# sensors.net
KiCad netlist of a schematic drawn in Altium Designer
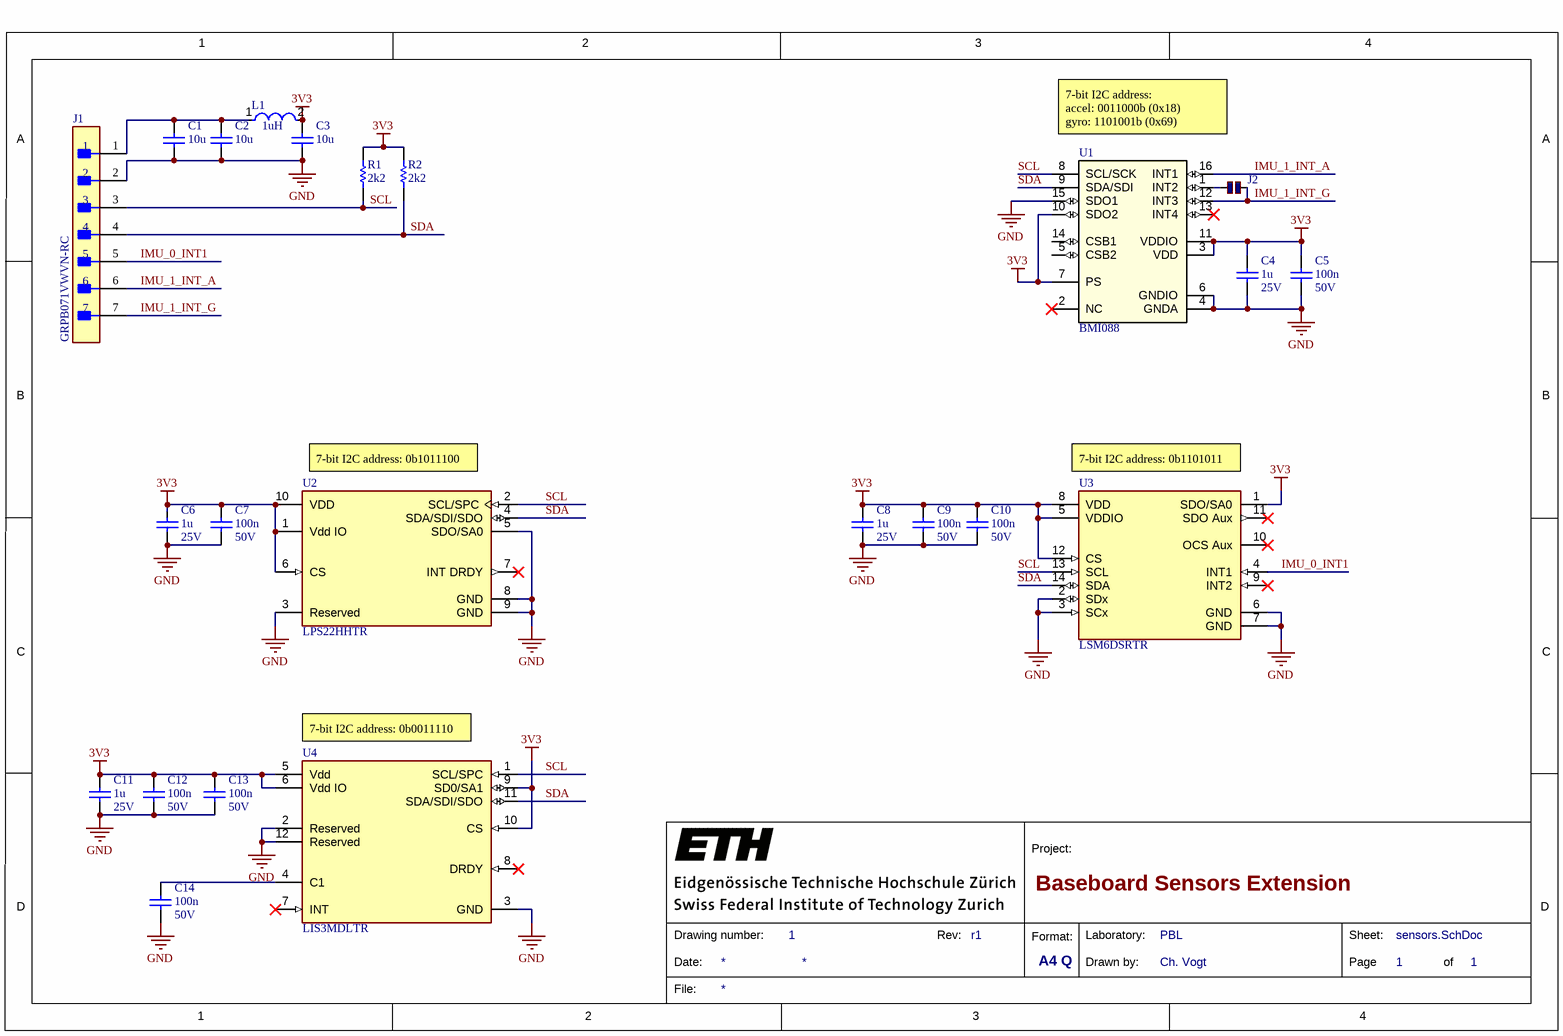
[diagram p0: sensors.SchDoc]

(export (version "E")
  (design (tool "Eeschema 10.0.6"))
  (components
    (comp (ref "C1")
      (value "10u")
      (footprint "k26_FPGA_drone_baseboard:CAPC0402")
      (fields
        (field (name "MANUFACTURER") "Samsung")
        (field (name "MANUFACTURER PART NUMBER") "CL05A106MP5NUNC")
      )
      (libsource (lib "k26_FPGA_drone_baseboard") (part "cap0402"))
    )
    (comp (ref "C2")
      (value "10u")
      (footprint "k26_FPGA_drone_baseboard:CAPC0402")
      (fields
        (field (name "MANUFACTURER") "Samsung")
        (field (name "MANUFACTURER PART NUMBER") "CL05A106MP5NUNC")
      )
      (libsource (lib "k26_FPGA_drone_baseboard") (part "cap0402"))
    )
    (comp (ref "C3")
      (value "10u")
      (footprint "k26_FPGA_drone_baseboard:CAPC0402")
      (fields
        (field (name "MANUFACTURER") "Samsung")
        (field (name "MANUFACTURER PART NUMBER") "CL05A106MP5NUNC")
      )
      (libsource (lib "k26_FPGA_drone_baseboard") (part "cap0402"))
    )
    (comp (ref "C4")
      (value "1u")
      (footprint "k26_FPGA_drone_baseboard:CAPC0402")
      (fields
        (field (name "MANUFACTURER") "Taiyo Yuden")
        (field (name "MANUFACTURER PART NUMBER") "TMK105BJ105MV-F")
        (field (name "RATED DC VOLTAGE (URDC)") "25V")
      )
      (libsource (lib "k26_FPGA_drone_baseboard") (part "cap0402"))
    )
    (comp (ref "C5")
      (value "100n")
      (footprint "k26_FPGA_drone_baseboard:CAPC0402")
      (fields
        (field (name "MANUFACTURER") "Yageo")
        (field (name "MANUFACTURER PART NUMBER") "CC0402KRX5R9BB104")
        (field (name "RATED DC VOLTAGE (URDC)") "50V")
      )
      (libsource (lib "k26_FPGA_drone_baseboard") (part "cap0402"))
    )
    (comp (ref "C6")
      (value "1u")
      (footprint "k26_FPGA_drone_baseboard:CAPC0402")
      (fields
        (field (name "MANUFACTURER") "Taiyo Yuden")
        (field (name "MANUFACTURER PART NUMBER") "TMK105BJ105MV-F")
        (field (name "RATED DC VOLTAGE (URDC)") "25V")
      )
      (libsource (lib "k26_FPGA_drone_baseboard") (part "cap0402"))
    )
    (comp (ref "C7")
      (value "100n")
      (footprint "k26_FPGA_drone_baseboard:CAPC0402")
      (fields
        (field (name "MANUFACTURER") "Yageo")
        (field (name "MANUFACTURER PART NUMBER") "CC0402KRX5R9BB104")
        (field (name "RATED DC VOLTAGE (URDC)") "50V")
      )
      (libsource (lib "k26_FPGA_drone_baseboard") (part "cap0402"))
    )
    (comp (ref "C8")
      (value "1u")
      (footprint "k26_FPGA_drone_baseboard:CAPC0402")
      (fields
        (field (name "MANUFACTURER") "Taiyo Yuden")
        (field (name "MANUFACTURER PART NUMBER") "TMK105BJ105MV-F")
        (field (name "RATED DC VOLTAGE (URDC)") "25V")
      )
      (libsource (lib "k26_FPGA_drone_baseboard") (part "cap0402"))
    )
    (comp (ref "C9")
      (value "100n")
      (footprint "k26_FPGA_drone_baseboard:CAPC0402")
      (fields
        (field (name "MANUFACTURER") "Yageo")
        (field (name "MANUFACTURER PART NUMBER") "CC0402KRX5R9BB104")
        (field (name "RATED DC VOLTAGE (URDC)") "50V")
      )
      (libsource (lib "k26_FPGA_drone_baseboard") (part "cap0402"))
    )
    (comp (ref "C10")
      (value "100n")
      (footprint "k26_FPGA_drone_baseboard:CAPC0402")
      (fields
        (field (name "MANUFACTURER") "Yageo")
        (field (name "MANUFACTURER PART NUMBER") "CC0402KRX5R9BB104")
        (field (name "RATED DC VOLTAGE (URDC)") "50V")
      )
      (libsource (lib "k26_FPGA_drone_baseboard") (part "cap0402"))
    )
    (comp (ref "C11")
      (value "1u")
      (footprint "k26_FPGA_drone_baseboard:CAPC0402")
      (fields
        (field (name "MANUFACTURER") "Taiyo Yuden")
        (field (name "MANUFACTURER PART NUMBER") "TMK105BJ105MV-F")
        (field (name "RATED DC VOLTAGE (URDC)") "25V")
      )
      (libsource (lib "k26_FPGA_drone_baseboard") (part "cap0402"))
    )
    (comp (ref "C12")
      (value "100n")
      (footprint "k26_FPGA_drone_baseboard:CAPC0402")
      (fields
        (field (name "MANUFACTURER") "Yageo")
        (field (name "MANUFACTURER PART NUMBER") "CC0402KRX5R9BB104")
        (field (name "RATED DC VOLTAGE (URDC)") "50V")
      )
      (libsource (lib "k26_FPGA_drone_baseboard") (part "cap0402"))
    )
    (comp (ref "C13")
      (value "100n")
      (footprint "k26_FPGA_drone_baseboard:CAPC0402")
      (fields
        (field (name "MANUFACTURER") "Yageo")
        (field (name "MANUFACTURER PART NUMBER") "CC0402KRX5R9BB104")
        (field (name "RATED DC VOLTAGE (URDC)") "50V")
      )
      (libsource (lib "k26_FPGA_drone_baseboard") (part "cap0402"))
    )
    (comp (ref "C14")
      (value "100n")
      (footprint "k26_FPGA_drone_baseboard:CAPC0402")
      (fields
        (field (name "MANUFACTURER") "Yageo")
        (field (name "MANUFACTURER PART NUMBER") "CC0402KRX5R9BB104")
        (field (name "RATED DC VOLTAGE (URDC)") "50V")
      )
      (libsource (lib "k26_FPGA_drone_baseboard") (part "cap0402"))
    )
    (comp (ref "J1")
      (value "GRPB071VWVN-RC")
      (footprint "FP-GRPB071VWVN-RC-MFG")
      (description "CONN HEADER VERT 7POS 1.27MM")
      (libsource (lib "Altium Content Vault") (part "5bcee6b94e1fee4be3f4cc3a650a442"))
    )
    (comp (ref "J2")
      (value "Solder Jumper")
      (footprint "Small Solder Jumper")
      (libsource (lib "ETHZ Vault") (part "Solder Jumper"))
    )
    (comp (ref "L1")
      (value "MLZ1005M1R0WT000")
      (footprint "FP-MLZ1005-MFG")
      (description "Shielded Multilayer Inductor 1uH ±20% 450mA 455mΩ SMD 0402")
      (fields (field (name "TOLERANCE") "20%") (field (name "INDUCTANCE") "1uH"))
      (libsource (lib "Altium Content Vault") (part "725321dda6339637d4d059423bc1c3c"))
    )
    (comp (ref "R1")
      (value "2k2")
      (footprint "k26_FPGA_drone_baseboard:RES0402")
      (fields
        (field (name "MANUFACTURER") "Vishay")
        (field (name "MANUFACTURER PART NUMBER") "CRCW04022K20FKED")
        (field (name "TOLERANCE") "1%")
      )
      (libsource (lib "k26_FPGA_drone_baseboard") (part "res0402"))
    )
    (comp (ref "R2")
      (value "2k2")
      (footprint "k26_FPGA_drone_baseboard:RES0402")
      (fields
        (field (name "MANUFACTURER") "Vishay")
        (field (name "MANUFACTURER PART NUMBER") "CRCW04022K20FKED")
        (field (name "TOLERANCE") "1%")
      )
      (libsource (lib "k26_FPGA_drone_baseboard") (part "res0402"))
    )
    (comp (ref "U1")
      (value "BMI088")
      (footprint "QFN_BMI085_BOS")
      (description "No Description Available")
      (fields (field (name "COPYRIGHT") "Copyright (C) 2024 Ultra Librarian. All rights reserved."))
      (libsource (lib "k26_FPGA_drone_baseboard") (part "BMI088"))
    )
    (comp (ref "U2")
      (value "LPS22HHTR")
      (footprint "FP-HLGA-10L-DM00386636-MFG")
      (description "CONSUMER MEMS")
      (fields
        (field (name "OCTOPART") "https://octopart.com/lps22hhtr-stmicroelectronics-94834025")
        (field (name "MANUFACTURER") "STMicroelectronics")
      )
      (libsource (lib "k26_FPGA_drone_baseboard") (part "af158f922cca5ffd55045a3797efeaf"))
    )
    (comp (ref "U3")
      (value "LSM6DSRTR")
      (footprint "FP-LGA-14L-DM00249496-MFG")
      (description "INEMO INERTIAL MODULE: 3D ACCELE")
      (fields
        (field (name "MANUFACTURER") "STMicroelectronics")
        (field (name "OCTOPART") "https://octopart.com/lsm6dsrtr-stmicroelectronics-93180177")
      )
      (libsource (lib "k26_FPGA_drone_baseboard") (part "CMP-12177-000003-1"))
    )
    (comp (ref "U4")
      (value "LIS3MDLTR")
      (footprint "FP-VFLGA-12-8365767-MFG")
      (description "SENSOR MR I2C/SPI 12LGA")
      (fields
        (field (name "OCTOPART") "https://octopart.com/lis3mdltr-stmicroelectronics-29403125")
        (field (name "MANUFACTURER") "STMicroelectronics")
      )
      (libsource (lib "k26_FPGA_drone_baseboard") (part "CMP-2000-07463-2"))
    )
  )
  (nets
    (net (code "1") (name "/IMU_0_INT1") (class "Default")
      (node (ref "J1") (pin "5") (pinfunction "5_5") (pintype "passive"))
      (node (ref "U3") (pin "4") (pinfunction "INT1_4") (pintype "input"))
    )
    (net (code "2") (name "/IMU_1_INT_A") (class "Default")
      (node (ref "J1") (pin "6") (pinfunction "6_6") (pintype "passive"))
      (node (ref "U1") (pin "16") (pinfunction "INT1_16") (pintype "bidirectional"))
    )
    (net (code "3") (name "/IMU_1_INT_G") (class "Default")
      (node (ref "J1") (pin "7") (pinfunction "7_7") (pintype "passive"))
      (node (ref "J2") (pin "1") (pintype "passive"))
      (node (ref "U1") (pin "12") (pinfunction "INT3_12") (pintype "bidirectional"))
    )
    (net (code "4") (name "/SCL") (class "Default")
      (node (ref "J1") (pin "3") (pinfunction "3_3") (pintype "passive"))
      (node (ref "R1") (pin "1") (pinfunction "1_1") (pintype "passive"))
      (node (ref "U1") (pin "8") (pinfunction "SCL/SCK_8") (pintype "passive"))
      (node (ref "U2") (pin "2") (pinfunction "SCL/SPC_2") (pintype "input"))
      (node (ref "U3") (pin "13") (pinfunction "SCL_13") (pintype "input"))
      (node (ref "U4") (pin "1") (pinfunction "SCL/SPC_1") (pintype "input"))
    )
    (net (code "5") (name "/SDA") (class "Default")
      (node (ref "J1") (pin "4") (pinfunction "4_4") (pintype "passive"))
      (node (ref "R2") (pin "1") (pinfunction "1_1") (pintype "passive"))
      (node (ref "U1") (pin "9") (pinfunction "SDA/SDI_9") (pintype "passive"))
      (node (ref "U2") (pin "4") (pinfunction "SDA/SDI/SDO_4") (pintype "bidirectional"))
      (node (ref "U3") (pin "14") (pinfunction "SDA_14") (pintype "bidirectional"))
      (node (ref "U4") (pin "11") (pinfunction "SDA/SDI/SDO_11") (pintype "bidirectional"))
    )
    (net (code "6") (name "3V3") (class "Default")
      (node (ref "C10") (pin "2") (pinfunction "2_2") (pintype "passive"))
      (node (ref "C11") (pin "2") (pinfunction "2_2") (pintype "passive"))
      (node (ref "C12") (pin "2") (pinfunction "2_2") (pintype "passive"))
      (node (ref "C13") (pin "2") (pinfunction "2_2") (pintype "passive"))
      (node (ref "C3") (pin "2") (pinfunction "2_2") (pintype "passive"))
      (node (ref "C4") (pin "2") (pinfunction "2_2") (pintype "passive"))
      (node (ref "C5") (pin "2") (pinfunction "2_2") (pintype "passive"))
      (node (ref "C6") (pin "2") (pinfunction "2_2") (pintype "passive"))
      (node (ref "C7") (pin "2") (pinfunction "2_2") (pintype "passive"))
      (node (ref "C8") (pin "2") (pinfunction "2_2") (pintype "passive"))
      (node (ref "C9") (pin "2") (pinfunction "2_2") (pintype "passive"))
      (node (ref "L1") (pin "2") (pinfunction "2_2") (pintype "passive"))
      (node (ref "R1") (pin "2") (pinfunction "2_2") (pintype "passive"))
      (node (ref "R2") (pin "2") (pinfunction "2_2") (pintype "passive"))
      (node (ref "U1") (pin "10") (pinfunction "SDO2_10") (pintype "bidirectional"))
      (node (ref "U1") (pin "11") (pinfunction "VDDIO_11") (pintype "power_in"))
      (node (ref "U1") (pin "3") (pinfunction "VDD_3") (pintype "power_in"))
      (node (ref "U1") (pin "7") (pinfunction "PS_7") (pintype "passive"))
      (node (ref "U2") (pin "1") (pinfunction "Vdd_IO_1") (pintype "power_in"))
      (node (ref "U2") (pin "10") (pinfunction "VDD_10") (pintype "power_in"))
      (node (ref "U2") (pin "6") (pinfunction "CS_6") (pintype "input"))
      (node (ref "U3") (pin "1") (pinfunction "SDO/SA0_1") (pintype "passive"))
      (node (ref "U3") (pin "12") (pinfunction "CS_12") (pintype "input"))
      (node (ref "U3") (pin "5") (pinfunction "VDDIO_5") (pintype "power_in"))
      (node (ref "U3") (pin "8") (pinfunction "VDD_8") (pintype "power_in"))
      (node (ref "U4") (pin "10") (pinfunction "CS_10") (pintype "input"))
      (node (ref "U4") (pin "5") (pinfunction "Vdd_5") (pintype "power_in"))
      (node (ref "U4") (pin "6") (pinfunction "Vdd_IO_6") (pintype "power_in"))
      (node (ref "U4") (pin "9") (pinfunction "SD0/SA1_9") (pintype "bidirectional"))
    )
    (net (code "7") (name "GND") (class "Default")
      (node (ref "C1") (pin "1") (pinfunction "1_1") (pintype "passive"))
      (node (ref "C10") (pin "1") (pinfunction "1_1") (pintype "passive"))
      (node (ref "C11") (pin "1") (pinfunction "1_1") (pintype "passive"))
      (node (ref "C12") (pin "1") (pinfunction "1_1") (pintype "passive"))
      (node (ref "C13") (pin "1") (pinfunction "1_1") (pintype "passive"))
      (node (ref "C14") (pin "1") (pinfunction "1_1") (pintype "passive"))
      (node (ref "C2") (pin "1") (pinfunction "1_1") (pintype "passive"))
      (node (ref "C3") (pin "1") (pinfunction "1_1") (pintype "passive"))
      (node (ref "C4") (pin "1") (pinfunction "1_1") (pintype "passive"))
      (node (ref "C5") (pin "1") (pinfunction "1_1") (pintype "passive"))
      (node (ref "C6") (pin "1") (pinfunction "1_1") (pintype "passive"))
      (node (ref "C7") (pin "1") (pinfunction "1_1") (pintype "passive"))
      (node (ref "C8") (pin "1") (pinfunction "1_1") (pintype "passive"))
      (node (ref "C9") (pin "1") (pinfunction "1_1") (pintype "passive"))
      (node (ref "J1") (pin "2") (pinfunction "2_2") (pintype "passive"))
      (node (ref "U1") (pin "15") (pinfunction "SDO1_15") (pintype "bidirectional"))
      (node (ref "U1") (pin "4") (pinfunction "GNDA_4") (pintype "power_in"))
      (node (ref "U1") (pin "6") (pinfunction "GNDIO_6") (pintype "power_in"))
      (node (ref "U2") (pin "3") (pinfunction "Reserved_3") (pintype "passive"))
      (node (ref "U2") (pin "5") (pinfunction "SDO/SA0_5") (pintype "passive"))
      (node (ref "U2") (pin "8") (pinfunction "GND_8") (pintype "power_in"))
      (node (ref "U2") (pin "9") (pinfunction "GND_9") (pintype "power_in"))
      (node (ref "U3") (pin "2") (pinfunction "SDx_2") (pintype "bidirectional"))
      (node (ref "U3") (pin "3") (pinfunction "SCx_3") (pintype "input"))
      (node (ref "U3") (pin "6") (pinfunction "GND_6") (pintype "power_in"))
      (node (ref "U3") (pin "7") (pinfunction "GND_7") (pintype "power_in"))
      (node (ref "U4") (pin "12") (pinfunction "Reserved_12") (pintype "passive"))
      (node (ref "U4") (pin "2") (pinfunction "Reserved_2") (pintype "passive"))
      (node (ref "U4") (pin "3") (pinfunction "GND_3") (pintype "power_in"))
    )
    (net (code "8") (name "Net-(C1-Pad2)") (class "Default")
      (node (ref "C1") (pin "2") (pinfunction "2_2") (pintype "passive"))
      (node (ref "C2") (pin "2") (pinfunction "2_2") (pintype "passive"))
      (node (ref "J1") (pin "1") (pinfunction "1_1") (pintype "passive"))
      (node (ref "L1") (pin "1") (pinfunction "1_1") (pintype "passive"))
    )
    (net (code "9") (name "Net-(U1-INT2)") (class "Default")
      (node (ref "J2") (pin "2") (pintype "passive"))
      (node (ref "U1") (pin "1") (pinfunction "INT2_1") (pintype "bidirectional"))
    )
    (net (code "10") (name "Net-(U4-C1)") (class "Default")
      (node (ref "C14") (pin "2") (pinfunction "2_2") (pintype "passive"))
      (node (ref "U4") (pin "4") (pinfunction "C1_4") (pintype "passive"))
    )
    (net (code "11") (name "unconnected-(U1-CSB1-Pad14)") (class "Default")
      (node (ref "U1") (pin "14") (pinfunction "CSB1_14") (pintype "bidirectional"))
    )
    (net (code "12") (name "unconnected-(U1-CSB2-Pad5)") (class "Default")
      (node (ref "U1") (pin "5") (pinfunction "CSB2_5") (pintype "bidirectional"))
    )
    (net (code "13") (name "unconnected-(U1-INT4-Pad13)") (class "Default")
      (node (ref "U1") (pin "13") (pinfunction "INT4_13") (pintype "bidirectional+no_connect"))
    )
    (net (code "14") (name "unconnected-(U1-NC-Pad2)") (class "Default")
      (node (ref "U1") (pin "2") (pinfunction "NC_2") (pintype "passive+no_connect"))
    )
    (net (code "15") (name "unconnected-(U2-INT_DRDY-Pad7)") (class "Default")
      (node (ref "U2") (pin "7") (pinfunction "INT_DRDY_7") (pintype "output+no_connect"))
    )
    (net (code "16") (name "unconnected-(U3-INT2-Pad9)") (class "Default")
      (node (ref "U3") (pin "9") (pinfunction "INT2_9") (pintype "input+no_connect"))
    )
    (net (code "17") (name "unconnected-(U3-OCS_Aux-Pad10)") (class "Default")
      (node (ref "U3") (pin "10") (pinfunction "OCS_Aux_10") (pintype "passive+no_connect"))
    )
    (net (code "18") (name "unconnected-(U3-SDO_Aux-Pad11)") (class "Default")
      (node (ref "U3") (pin "11") (pinfunction "SDO_Aux_11") (pintype "output+no_connect"))
    )
    (net (code "19") (name "unconnected-(U4-DRDY-Pad8)") (class "Default")
      (node (ref "U4") (pin "8") (pinfunction "DRDY_8") (pintype "input+no_connect"))
    )
    (net (code "20") (name "unconnected-(U4-INT-Pad7)") (class "Default")
      (node (ref "U4") (pin "7") (pinfunction "INT_7") (pintype "input+no_connect"))
    )
  )
)
